# PROB_S7CAS_DDR.net
KiCad netlist of a schematic drawn in Altium Designer
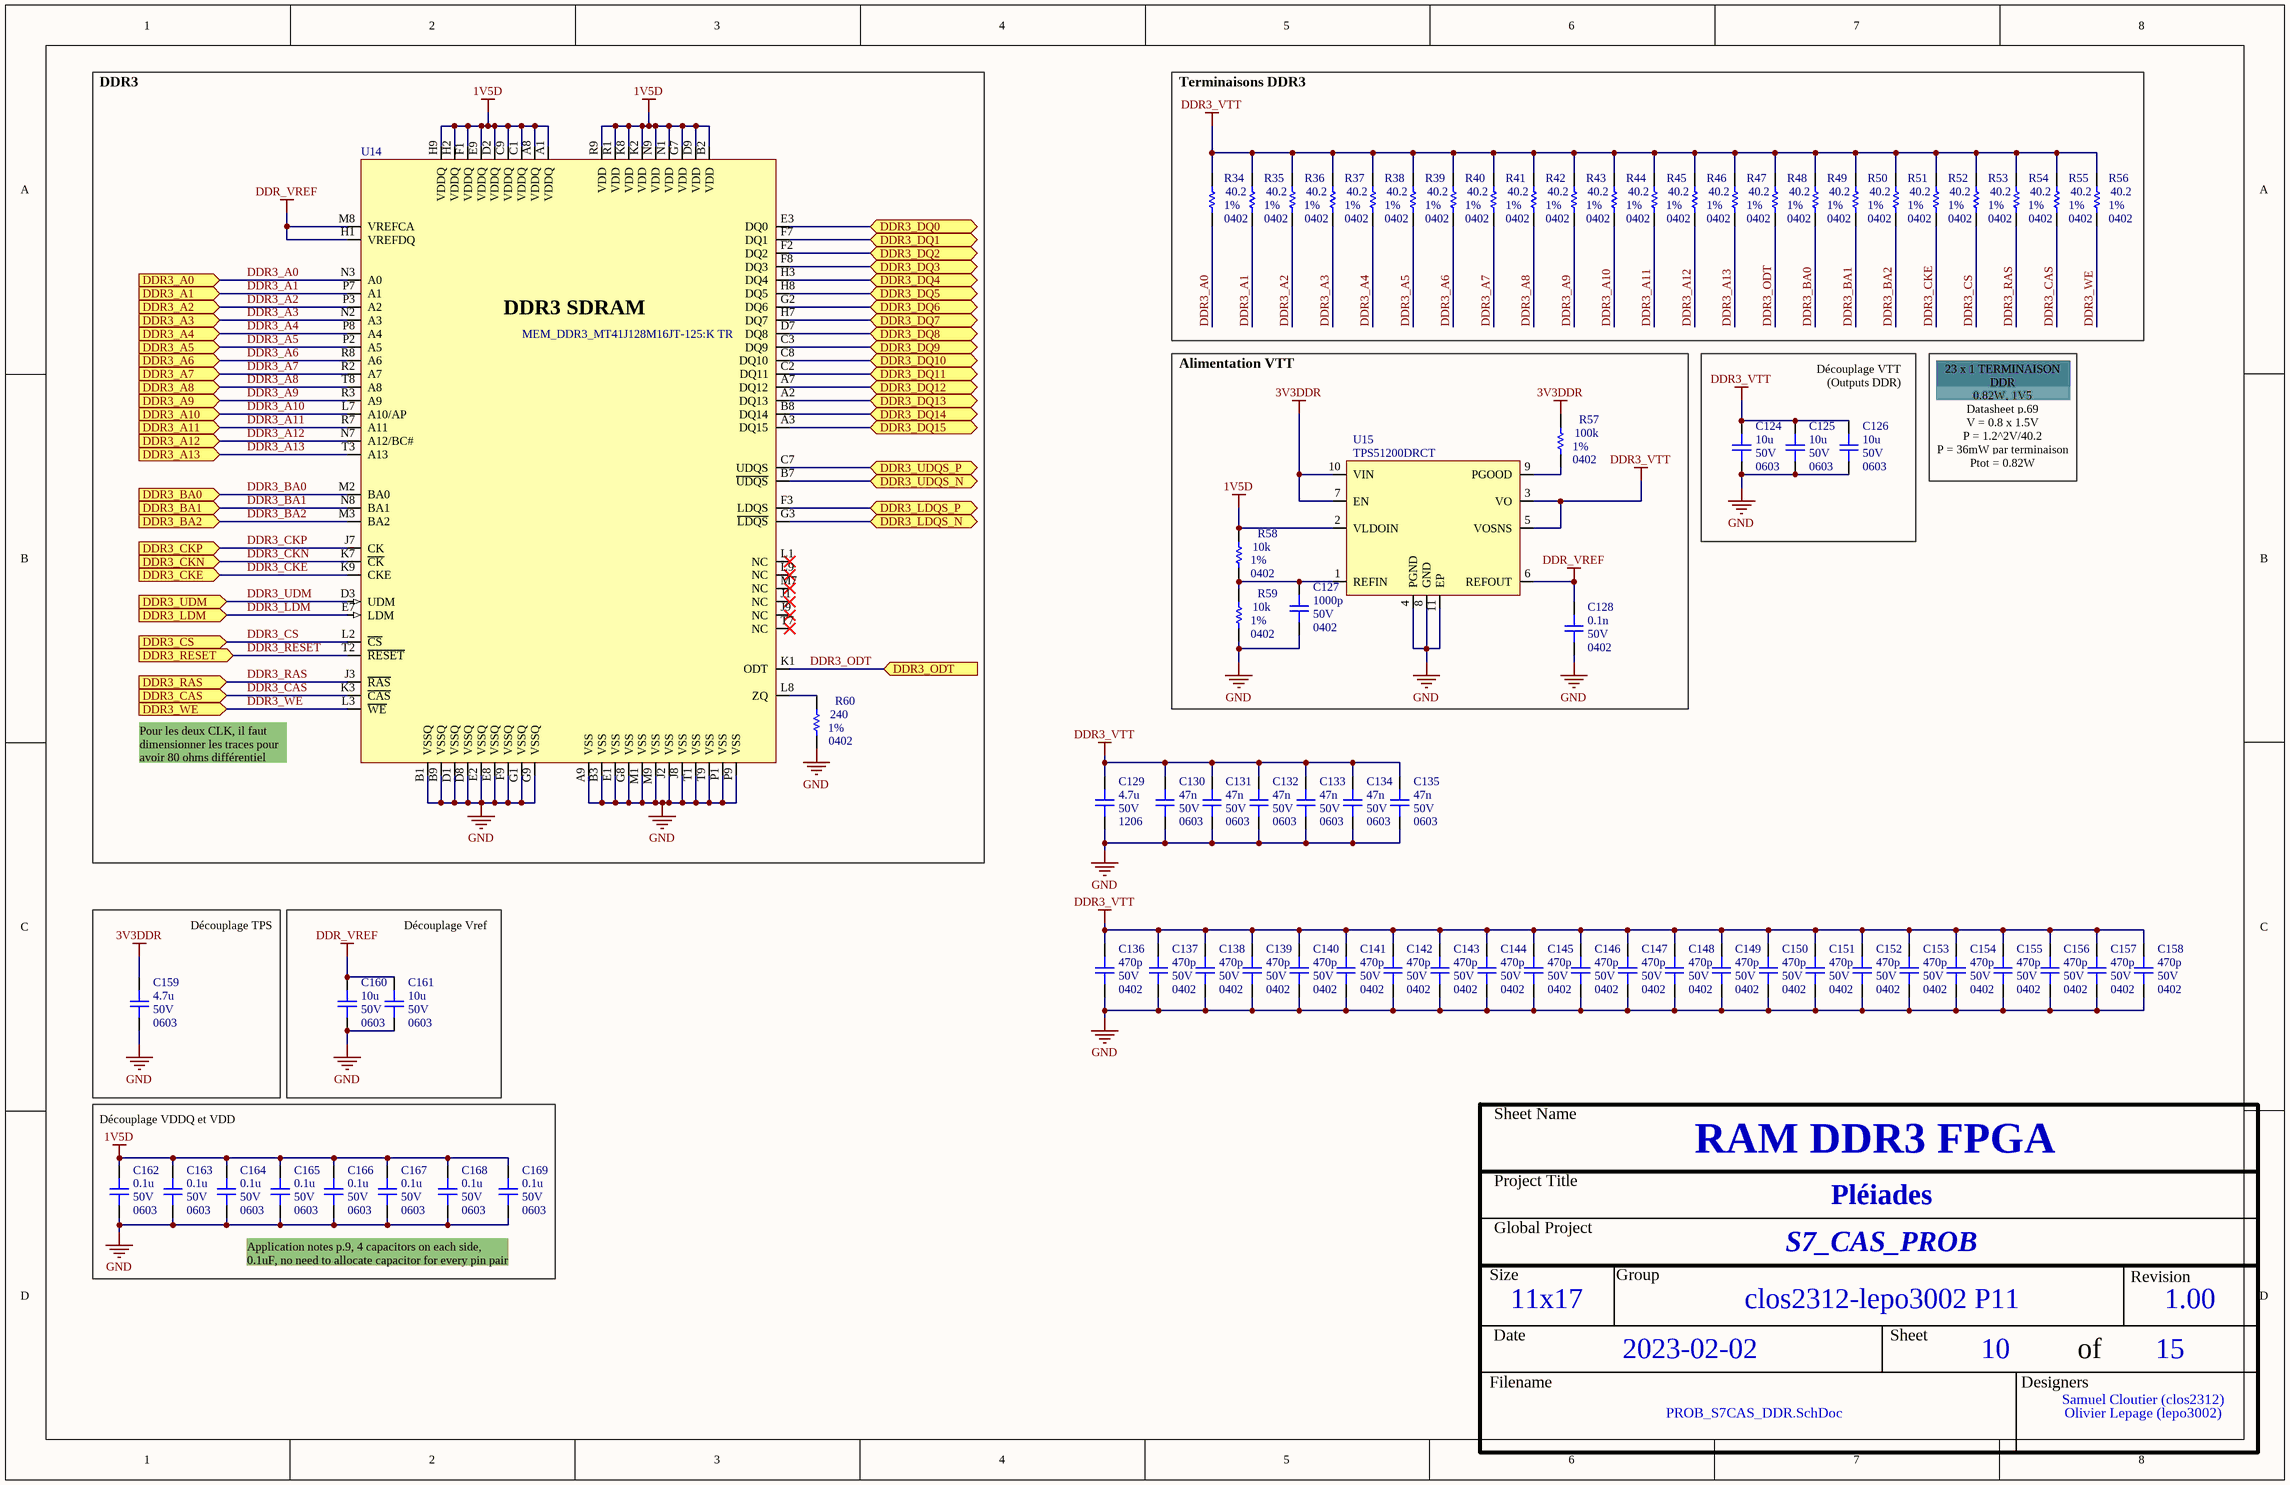
[diagram p0: PROB_S7CAS_DDR.SchDoc]

(export (version "E")
  (design (tool "Eeschema 10.0.6"))
  (components
    (comp (ref "C124")
      (value "10u")
      (footprint "CAP_0603")
      (description "CAP - 0603")
      (fields
        (field (name "VOLTAGE") "50V")
        (field (name "PACKAGE") "0603")
        (field (name "CREATEDBY") "Jonathan Bouchard")
      )
      (libsource (lib "S7CAS_LIB2021") (part "CAP - 0603"))
    )
    (comp (ref "C125")
      (value "10u")
      (footprint "CAP_0603")
      (description "CAP - 0603")
      (fields
        (field (name "VOLTAGE") "50V")
        (field (name "PACKAGE") "0603")
        (field (name "CREATEDBY") "Jonathan Bouchard")
      )
      (libsource (lib "S7CAS_LIB2021") (part "CAP - 0603"))
    )
    (comp (ref "C126")
      (value "10u")
      (footprint "CAP_0603")
      (description "CAP - 0603")
      (fields
        (field (name "VOLTAGE") "50V")
        (field (name "PACKAGE") "0603")
        (field (name "CREATEDBY") "Jonathan Bouchard")
      )
      (libsource (lib "S7CAS_LIB2021") (part "CAP - 0603"))
    )
    (comp (ref "C127")
      (value "1000p")
      (footprint "CAP_0402")
      (description "CAP - 0402")
      (fields
        (field (name "VOLTAGE") "50V")
        (field (name "PACKAGE") "0402")
        (field (name "CREATEDBY") "Jonathan Bouchard")
      )
      (libsource (lib "S7CAS_LIB2021") (part "CAP - 0402"))
    )
    (comp (ref "C128")
      (value "0.1n")
      (footprint "CAP_0402")
      (description "CAP - 0402")
      (fields
        (field (name "VOLTAGE") "50V")
        (field (name "PACKAGE") "0402")
        (field (name "CREATEDBY") "Jonathan Bouchard")
      )
      (libsource (lib "S7CAS_LIB2021") (part "CAP - 0402"))
    )
    (comp (ref "C129")
      (value "4.7u")
      (footprint "CAP_1206")
      (description "CAP - 1206")
      (fields
        (field (name "VOLTAGE") "50V")
        (field (name "PACKAGE") "1206")
        (field (name "CREATEDBY") "Jonathan Bouchard")
      )
      (libsource (lib "S7CAS_LIB2021") (part "CAP - 1206"))
    )
    (comp (ref "C130")
      (value "47n")
      (footprint "CAP_0603")
      (description "CAP - 0603")
      (fields
        (field (name "VOLTAGE") "50V")
        (field (name "PACKAGE") "0603")
        (field (name "CREATEDBY") "Jonathan Bouchard")
      )
      (libsource (lib "S7CAS_LIB2021") (part "CAP - 0603"))
    )
    (comp (ref "C131")
      (value "47n")
      (footprint "CAP_0603")
      (description "CAP - 0603")
      (fields
        (field (name "VOLTAGE") "50V")
        (field (name "PACKAGE") "0603")
        (field (name "CREATEDBY") "Jonathan Bouchard")
      )
      (libsource (lib "S7CAS_LIB2021") (part "CAP - 0603"))
    )
    (comp (ref "C132")
      (value "47n")
      (footprint "CAP_0603")
      (description "CAP - 0603")
      (fields
        (field (name "VOLTAGE") "50V")
        (field (name "PACKAGE") "0603")
        (field (name "CREATEDBY") "Jonathan Bouchard")
      )
      (libsource (lib "S7CAS_LIB2021") (part "CAP - 0603"))
    )
    (comp (ref "C133")
      (value "47n")
      (footprint "CAP_0603")
      (description "CAP - 0603")
      (fields
        (field (name "VOLTAGE") "50V")
        (field (name "PACKAGE") "0603")
        (field (name "CREATEDBY") "Jonathan Bouchard")
      )
      (libsource (lib "S7CAS_LIB2021") (part "CAP - 0603"))
    )
    (comp (ref "C134")
      (value "47n")
      (footprint "CAP_0603")
      (description "CAP - 0603")
      (fields
        (field (name "VOLTAGE") "50V")
        (field (name "PACKAGE") "0603")
        (field (name "CREATEDBY") "Jonathan Bouchard")
      )
      (libsource (lib "S7CAS_LIB2021") (part "CAP - 0603"))
    )
    (comp (ref "C135")
      (value "47n")
      (footprint "CAP_0603")
      (description "CAP - 0603")
      (fields
        (field (name "VOLTAGE") "50V")
        (field (name "PACKAGE") "0603")
        (field (name "CREATEDBY") "Jonathan Bouchard")
      )
      (libsource (lib "S7CAS_LIB2021") (part "CAP - 0603"))
    )
    (comp (ref "C136")
      (value "470p")
      (footprint "CAP_0402")
      (description "CAP - 0402")
      (fields
        (field (name "VOLTAGE") "50V")
        (field (name "PACKAGE") "0402")
        (field (name "CREATEDBY") "Jonathan Bouchard")
      )
      (libsource (lib "S7CAS_LIB2021") (part "CAP - 0402"))
    )
    (comp (ref "C137")
      (value "470p")
      (footprint "CAP_0402")
      (description "CAP - 0402")
      (fields
        (field (name "VOLTAGE") "50V")
        (field (name "PACKAGE") "0402")
        (field (name "CREATEDBY") "Jonathan Bouchard")
      )
      (libsource (lib "S7CAS_LIB2021") (part "CAP - 0402"))
    )
    (comp (ref "C138")
      (value "470p")
      (footprint "CAP_0402")
      (description "CAP - 0402")
      (fields
        (field (name "VOLTAGE") "50V")
        (field (name "PACKAGE") "0402")
        (field (name "CREATEDBY") "Jonathan Bouchard")
      )
      (libsource (lib "S7CAS_LIB2021") (part "CAP - 0402"))
    )
    (comp (ref "C139")
      (value "470p")
      (footprint "CAP_0402")
      (description "CAP - 0402")
      (fields
        (field (name "VOLTAGE") "50V")
        (field (name "PACKAGE") "0402")
        (field (name "CREATEDBY") "Jonathan Bouchard")
      )
      (libsource (lib "S7CAS_LIB2021") (part "CAP - 0402"))
    )
    (comp (ref "C140")
      (value "470p")
      (footprint "CAP_0402")
      (description "CAP - 0402")
      (fields
        (field (name "VOLTAGE") "50V")
        (field (name "PACKAGE") "0402")
        (field (name "CREATEDBY") "Jonathan Bouchard")
      )
      (libsource (lib "S7CAS_LIB2021") (part "CAP - 0402"))
    )
    (comp (ref "C141")
      (value "470p")
      (footprint "CAP_0402")
      (description "CAP - 0402")
      (fields
        (field (name "VOLTAGE") "50V")
        (field (name "PACKAGE") "0402")
        (field (name "CREATEDBY") "Jonathan Bouchard")
      )
      (libsource (lib "S7CAS_LIB2021") (part "CAP - 0402"))
    )
    (comp (ref "C142")
      (value "470p")
      (footprint "CAP_0402")
      (description "CAP - 0402")
      (fields
        (field (name "VOLTAGE") "50V")
        (field (name "PACKAGE") "0402")
        (field (name "CREATEDBY") "Jonathan Bouchard")
      )
      (libsource (lib "S7CAS_LIB2021") (part "CAP - 0402"))
    )
    (comp (ref "C143")
      (value "470p")
      (footprint "CAP_0402")
      (description "CAP - 0402")
      (fields
        (field (name "VOLTAGE") "50V")
        (field (name "PACKAGE") "0402")
        (field (name "CREATEDBY") "Jonathan Bouchard")
      )
      (libsource (lib "S7CAS_LIB2021") (part "CAP - 0402"))
    )
    (comp (ref "C144")
      (value "470p")
      (footprint "CAP_0402")
      (description "CAP - 0402")
      (fields
        (field (name "VOLTAGE") "50V")
        (field (name "PACKAGE") "0402")
        (field (name "CREATEDBY") "Jonathan Bouchard")
      )
      (libsource (lib "S7CAS_LIB2021") (part "CAP - 0402"))
    )
    (comp (ref "C145")
      (value "470p")
      (footprint "CAP_0402")
      (description "CAP - 0402")
      (fields
        (field (name "VOLTAGE") "50V")
        (field (name "PACKAGE") "0402")
        (field (name "CREATEDBY") "Jonathan Bouchard")
      )
      (libsource (lib "S7CAS_LIB2021") (part "CAP - 0402"))
    )
    (comp (ref "C146")
      (value "470p")
      (footprint "CAP_0402")
      (description "CAP - 0402")
      (fields
        (field (name "VOLTAGE") "50V")
        (field (name "PACKAGE") "0402")
        (field (name "CREATEDBY") "Jonathan Bouchard")
      )
      (libsource (lib "S7CAS_LIB2021") (part "CAP - 0402"))
    )
    (comp (ref "C147")
      (value "470p")
      (footprint "CAP_0402")
      (description "CAP - 0402")
      (fields
        (field (name "VOLTAGE") "50V")
        (field (name "PACKAGE") "0402")
        (field (name "CREATEDBY") "Jonathan Bouchard")
      )
      (libsource (lib "S7CAS_LIB2021") (part "CAP - 0402"))
    )
    (comp (ref "C148")
      (value "470p")
      (footprint "CAP_0402")
      (description "CAP - 0402")
      (fields
        (field (name "VOLTAGE") "50V")
        (field (name "PACKAGE") "0402")
        (field (name "CREATEDBY") "Jonathan Bouchard")
      )
      (libsource (lib "S7CAS_LIB2021") (part "CAP - 0402"))
    )
    (comp (ref "C149")
      (value "470p")
      (footprint "CAP_0402")
      (description "CAP - 0402")
      (fields
        (field (name "VOLTAGE") "50V")
        (field (name "PACKAGE") "0402")
        (field (name "CREATEDBY") "Jonathan Bouchard")
      )
      (libsource (lib "S7CAS_LIB2021") (part "CAP - 0402"))
    )
    (comp (ref "C150")
      (value "470p")
      (footprint "CAP_0402")
      (description "CAP - 0402")
      (fields
        (field (name "VOLTAGE") "50V")
        (field (name "PACKAGE") "0402")
        (field (name "CREATEDBY") "Jonathan Bouchard")
      )
      (libsource (lib "S7CAS_LIB2021") (part "CAP - 0402"))
    )
    (comp (ref "C151")
      (value "470p")
      (footprint "CAP_0402")
      (description "CAP - 0402")
      (fields
        (field (name "VOLTAGE") "50V")
        (field (name "PACKAGE") "0402")
        (field (name "CREATEDBY") "Jonathan Bouchard")
      )
      (libsource (lib "S7CAS_LIB2021") (part "CAP - 0402"))
    )
    (comp (ref "C152")
      (value "470p")
      (footprint "CAP_0402")
      (description "CAP - 0402")
      (fields
        (field (name "VOLTAGE") "50V")
        (field (name "PACKAGE") "0402")
        (field (name "CREATEDBY") "Jonathan Bouchard")
      )
      (libsource (lib "S7CAS_LIB2021") (part "CAP - 0402"))
    )
    (comp (ref "C153")
      (value "470p")
      (footprint "CAP_0402")
      (description "CAP - 0402")
      (fields
        (field (name "VOLTAGE") "50V")
        (field (name "PACKAGE") "0402")
        (field (name "CREATEDBY") "Jonathan Bouchard")
      )
      (libsource (lib "S7CAS_LIB2021") (part "CAP - 0402"))
    )
    (comp (ref "C154")
      (value "470p")
      (footprint "CAP_0402")
      (description "CAP - 0402")
      (fields
        (field (name "VOLTAGE") "50V")
        (field (name "PACKAGE") "0402")
        (field (name "CREATEDBY") "Jonathan Bouchard")
      )
      (libsource (lib "S7CAS_LIB2021") (part "CAP - 0402"))
    )
    (comp (ref "C155")
      (value "470p")
      (footprint "CAP_0402")
      (description "CAP - 0402")
      (fields
        (field (name "VOLTAGE") "50V")
        (field (name "PACKAGE") "0402")
        (field (name "CREATEDBY") "Jonathan Bouchard")
      )
      (libsource (lib "S7CAS_LIB2021") (part "CAP - 0402"))
    )
    (comp (ref "C156")
      (value "470p")
      (footprint "CAP_0402")
      (description "CAP - 0402")
      (fields
        (field (name "VOLTAGE") "50V")
        (field (name "PACKAGE") "0402")
        (field (name "CREATEDBY") "Jonathan Bouchard")
      )
      (libsource (lib "S7CAS_LIB2021") (part "CAP - 0402"))
    )
    (comp (ref "C157")
      (value "470p")
      (footprint "CAP_0402")
      (description "CAP - 0402")
      (fields
        (field (name "VOLTAGE") "50V")
        (field (name "PACKAGE") "0402")
        (field (name "CREATEDBY") "Jonathan Bouchard")
      )
      (libsource (lib "S7CAS_LIB2021") (part "CAP - 0402"))
    )
    (comp (ref "C158")
      (value "470p")
      (footprint "CAP_0402")
      (description "CAP - 0402")
      (fields
        (field (name "VOLTAGE") "50V")
        (field (name "PACKAGE") "0402")
        (field (name "CREATEDBY") "Jonathan Bouchard")
      )
      (libsource (lib "S7CAS_LIB2021") (part "CAP - 0402"))
    )
    (comp (ref "C159")
      (value "4.7u")
      (footprint "CAP_0603")
      (description "CAP - 0603")
      (fields
        (field (name "VOLTAGE") "50V")
        (field (name "PACKAGE") "0603")
        (field (name "CREATEDBY") "Jonathan Bouchard")
      )
      (libsource (lib "S7CAS_LIB2021") (part "CAP - 0603"))
    )
    (comp (ref "C160")
      (value "10u")
      (footprint "CAP_0603")
      (description "CAP - 0603")
      (fields
        (field (name "VOLTAGE") "50V")
        (field (name "PACKAGE") "0603")
        (field (name "CREATEDBY") "Jonathan Bouchard")
      )
      (libsource (lib "S7CAS_LIB2021") (part "CAP - 0603"))
    )
    (comp (ref "C161")
      (value "10u")
      (footprint "CAP_0603")
      (description "CAP - 0603")
      (fields
        (field (name "VOLTAGE") "50V")
        (field (name "PACKAGE") "0603")
        (field (name "CREATEDBY") "Jonathan Bouchard")
      )
      (libsource (lib "S7CAS_LIB2021") (part "CAP - 0603"))
    )
    (comp (ref "C162")
      (value "0.1u")
      (footprint "CAP_0603")
      (description "CAP - 0603")
      (fields
        (field (name "VOLTAGE") "50V")
        (field (name "PACKAGE") "0603")
        (field (name "CREATEDBY") "Jonathan Bouchard")
      )
      (libsource (lib "S7CAS_LIB2021") (part "CAP - 0603"))
    )
    (comp (ref "C163")
      (value "0.1u")
      (footprint "CAP_0603")
      (description "CAP - 0603")
      (fields
        (field (name "VOLTAGE") "50V")
        (field (name "PACKAGE") "0603")
        (field (name "CREATEDBY") "Jonathan Bouchard")
      )
      (libsource (lib "S7CAS_LIB2021") (part "CAP - 0603"))
    )
    (comp (ref "C164")
      (value "0.1u")
      (footprint "CAP_0603")
      (description "CAP - 0603")
      (fields
        (field (name "VOLTAGE") "50V")
        (field (name "PACKAGE") "0603")
        (field (name "CREATEDBY") "Jonathan Bouchard")
      )
      (libsource (lib "S7CAS_LIB2021") (part "CAP - 0603"))
    )
    (comp (ref "C165")
      (value "0.1u")
      (footprint "CAP_0603")
      (description "CAP - 0603")
      (fields
        (field (name "VOLTAGE") "50V")
        (field (name "PACKAGE") "0603")
        (field (name "CREATEDBY") "Jonathan Bouchard")
      )
      (libsource (lib "S7CAS_LIB2021") (part "CAP - 0603"))
    )
    (comp (ref "C166")
      (value "0.1u")
      (footprint "CAP_0603")
      (description "CAP - 0603")
      (fields
        (field (name "VOLTAGE") "50V")
        (field (name "PACKAGE") "0603")
        (field (name "CREATEDBY") "Jonathan Bouchard")
      )
      (libsource (lib "S7CAS_LIB2021") (part "CAP - 0603"))
    )
    (comp (ref "C167")
      (value "0.1u")
      (footprint "CAP_0603")
      (description "CAP - 0603")
      (fields
        (field (name "VOLTAGE") "50V")
        (field (name "PACKAGE") "0603")
        (field (name "CREATEDBY") "Jonathan Bouchard")
      )
      (libsource (lib "S7CAS_LIB2021") (part "CAP - 0603"))
    )
    (comp (ref "C168")
      (value "0.1u")
      (footprint "CAP_0603")
      (description "CAP - 0603")
      (fields
        (field (name "VOLTAGE") "50V")
        (field (name "PACKAGE") "0603")
        (field (name "CREATEDBY") "Jonathan Bouchard")
      )
      (libsource (lib "S7CAS_LIB2021") (part "CAP - 0603"))
    )
    (comp (ref "C169")
      (value "0.1u")
      (footprint "CAP_0603")
      (description "CAP - 0603")
      (fields
        (field (name "VOLTAGE") "50V")
        (field (name "PACKAGE") "0603")
        (field (name "CREATEDBY") "Jonathan Bouchard")
      )
      (libsource (lib "S7CAS_LIB2021") (part "CAP - 0603"))
    )
    (comp (ref "R34")
      (value "40.2")
      (footprint "RES_0402")
      (description "RES - 0402")
      (fields
        (field (name "VOLTAGE") "50V")
        (field (name "POWER") "1/16W")
        (field (name "PACKAGE") "0402")
        (field (name "PRECISION") "1%")
        (field (name "CREATEDBY") "Jonathan Bouchard")
      )
      (libsource (lib "S7CAS_LIB2021") (part "RES - 0402"))
    )
    (comp (ref "R35")
      (value "40.2")
      (footprint "RES_0402")
      (description "RES - 0402")
      (fields
        (field (name "VOLTAGE") "50V")
        (field (name "POWER") "1/16W")
        (field (name "PACKAGE") "0402")
        (field (name "PRECISION") "1%")
        (field (name "CREATEDBY") "Jonathan Bouchard")
      )
      (libsource (lib "S7CAS_LIB2021") (part "RES - 0402"))
    )
    (comp (ref "R36")
      (value "40.2")
      (footprint "RES_0402")
      (description "RES - 0402")
      (fields
        (field (name "VOLTAGE") "50V")
        (field (name "POWER") "1/16W")
        (field (name "PACKAGE") "0402")
        (field (name "PRECISION") "1%")
        (field (name "CREATEDBY") "Jonathan Bouchard")
      )
      (libsource (lib "S7CAS_LIB2021") (part "RES - 0402"))
    )
    (comp (ref "R37")
      (value "40.2")
      (footprint "RES_0402")
      (description "RES - 0402")
      (fields
        (field (name "VOLTAGE") "50V")
        (field (name "POWER") "1/16W")
        (field (name "PACKAGE") "0402")
        (field (name "PRECISION") "1%")
        (field (name "CREATEDBY") "Jonathan Bouchard")
      )
      (libsource (lib "S7CAS_LIB2021") (part "RES - 0402"))
    )
    (comp (ref "R38")
      (value "40.2")
      (footprint "RES_0402")
      (description "RES - 0402")
      (fields
        (field (name "VOLTAGE") "50V")
        (field (name "POWER") "1/16W")
        (field (name "PACKAGE") "0402")
        (field (name "PRECISION") "1%")
        (field (name "CREATEDBY") "Jonathan Bouchard")
      )
      (libsource (lib "S7CAS_LIB2021") (part "RES - 0402"))
    )
    (comp (ref "R39")
      (value "40.2")
      (footprint "RES_0402")
      (description "RES - 0402")
      (fields
        (field (name "VOLTAGE") "50V")
        (field (name "POWER") "1/16W")
        (field (name "PACKAGE") "0402")
        (field (name "PRECISION") "1%")
        (field (name "CREATEDBY") "Jonathan Bouchard")
      )
      (libsource (lib "S7CAS_LIB2021") (part "RES - 0402"))
    )
    (comp (ref "R40")
      (value "40.2")
      (footprint "RES_0402")
      (description "RES - 0402")
      (fields
        (field (name "VOLTAGE") "50V")
        (field (name "POWER") "1/16W")
        (field (name "PACKAGE") "0402")
        (field (name "PRECISION") "1%")
        (field (name "CREATEDBY") "Jonathan Bouchard")
      )
      (libsource (lib "S7CAS_LIB2021") (part "RES - 0402"))
    )
    (comp (ref "R41")
      (value "40.2")
      (footprint "RES_0402")
      (description "RES - 0402")
      (fields
        (field (name "VOLTAGE") "50V")
        (field (name "POWER") "1/16W")
        (field (name "PACKAGE") "0402")
        (field (name "PRECISION") "1%")
        (field (name "CREATEDBY") "Jonathan Bouchard")
      )
      (libsource (lib "S7CAS_LIB2021") (part "RES - 0402"))
    )
    (comp (ref "R42")
      (value "40.2")
      (footprint "RES_0402")
      (description "RES - 0402")
      (fields
        (field (name "VOLTAGE") "50V")
        (field (name "POWER") "1/16W")
        (field (name "PACKAGE") "0402")
        (field (name "PRECISION") "1%")
        (field (name "CREATEDBY") "Jonathan Bouchard")
      )
      (libsource (lib "S7CAS_LIB2021") (part "RES - 0402"))
    )
    (comp (ref "R43")
      (value "40.2")
      (footprint "RES_0402")
      (description "RES - 0402")
      (fields
        (field (name "VOLTAGE") "50V")
        (field (name "POWER") "1/16W")
        (field (name "PACKAGE") "0402")
        (field (name "PRECISION") "1%")
        (field (name "CREATEDBY") "Jonathan Bouchard")
      )
      (libsource (lib "S7CAS_LIB2021") (part "RES - 0402"))
    )
    (comp (ref "R44")
      (value "40.2")
      (footprint "RES_0402")
      (description "RES - 0402")
      (fields
        (field (name "VOLTAGE") "50V")
        (field (name "POWER") "1/16W")
        (field (name "PACKAGE") "0402")
        (field (name "PRECISION") "1%")
        (field (name "CREATEDBY") "Jonathan Bouchard")
      )
      (libsource (lib "S7CAS_LIB2021") (part "RES - 0402"))
    )
    (comp (ref "R45")
      (value "40.2")
      (footprint "RES_0402")
      (description "RES - 0402")
      (fields
        (field (name "VOLTAGE") "50V")
        (field (name "POWER") "1/16W")
        (field (name "PACKAGE") "0402")
        (field (name "PRECISION") "1%")
        (field (name "CREATEDBY") "Jonathan Bouchard")
      )
      (libsource (lib "S7CAS_LIB2021") (part "RES - 0402"))
    )
    (comp (ref "R46")
      (value "40.2")
      (footprint "RES_0402")
      (description "RES - 0402")
      (fields
        (field (name "VOLTAGE") "50V")
        (field (name "POWER") "1/16W")
        (field (name "PACKAGE") "0402")
        (field (name "PRECISION") "1%")
        (field (name "CREATEDBY") "Jonathan Bouchard")
      )
      (libsource (lib "S7CAS_LIB2021") (part "RES - 0402"))
    )
    (comp (ref "R47")
      (value "40.2")
      (footprint "RES_0402")
      (description "RES - 0402")
      (fields
        (field (name "VOLTAGE") "50V")
        (field (name "POWER") "1/16W")
        (field (name "PACKAGE") "0402")
        (field (name "PRECISION") "1%")
        (field (name "CREATEDBY") "Jonathan Bouchard")
      )
      (libsource (lib "S7CAS_LIB2021") (part "RES - 0402"))
    )
    (comp (ref "R48")
      (value "40.2")
      (footprint "RES_0402")
      (description "RES - 0402")
      (fields
        (field (name "VOLTAGE") "50V")
        (field (name "POWER") "1/16W")
        (field (name "PACKAGE") "0402")
        (field (name "PRECISION") "1%")
        (field (name "CREATEDBY") "Jonathan Bouchard")
      )
      (libsource (lib "S7CAS_LIB2021") (part "RES - 0402"))
    )
    (comp (ref "R49")
      (value "40.2")
      (footprint "RES_0402")
      (description "RES - 0402")
      (fields
        (field (name "VOLTAGE") "50V")
        (field (name "POWER") "1/16W")
        (field (name "PACKAGE") "0402")
        (field (name "PRECISION") "1%")
        (field (name "CREATEDBY") "Jonathan Bouchard")
      )
      (libsource (lib "S7CAS_LIB2021") (part "RES - 0402"))
    )
    (comp (ref "R50")
      (value "40.2")
      (footprint "RES_0402")
      (description "RES - 0402")
      (fields
        (field (name "VOLTAGE") "50V")
        (field (name "POWER") "1/16W")
        (field (name "PACKAGE") "0402")
        (field (name "PRECISION") "1%")
        (field (name "CREATEDBY") "Jonathan Bouchard")
      )
      (libsource (lib "S7CAS_LIB2021") (part "RES - 0402"))
    )
    (comp (ref "R51")
      (value "40.2")
      (footprint "RES_0402")
      (description "RES - 0402")
      (fields
        (field (name "VOLTAGE") "50V")
        (field (name "POWER") "1/16W")
        (field (name "PACKAGE") "0402")
        (field (name "PRECISION") "1%")
        (field (name "CREATEDBY") "Jonathan Bouchard")
      )
      (libsource (lib "S7CAS_LIB2021") (part "RES - 0402"))
    )
    (comp (ref "R52")
      (value "40.2")
      (footprint "RES_0402")
      (description "RES - 0402")
      (fields
        (field (name "VOLTAGE") "50V")
        (field (name "POWER") "1/16W")
        (field (name "PACKAGE") "0402")
        (field (name "PRECISION") "1%")
        (field (name "CREATEDBY") "Jonathan Bouchard")
      )
      (libsource (lib "S7CAS_LIB2021") (part "RES - 0402"))
    )
    (comp (ref "R53")
      (value "40.2")
      (footprint "RES_0402")
      (description "RES - 0402")
      (fields
        (field (name "VOLTAGE") "50V")
        (field (name "POWER") "1/16W")
        (field (name "PACKAGE") "0402")
        (field (name "PRECISION") "1%")
        (field (name "CREATEDBY") "Jonathan Bouchard")
      )
      (libsource (lib "S7CAS_LIB2021") (part "RES - 0402"))
    )
    (comp (ref "R54")
      (value "40.2")
      (footprint "RES_0402")
      (description "RES - 0402")
      (fields
        (field (name "VOLTAGE") "50V")
        (field (name "POWER") "1/16W")
        (field (name "PACKAGE") "0402")
        (field (name "PRECISION") "1%")
        (field (name "CREATEDBY") "Jonathan Bouchard")
      )
      (libsource (lib "S7CAS_LIB2021") (part "RES - 0402"))
    )
    (comp (ref "R55")
      (value "40.2")
      (footprint "RES_0402")
      (description "RES - 0402")
      (fields
        (field (name "VOLTAGE") "50V")
        (field (name "POWER") "1/16W")
        (field (name "PACKAGE") "0402")
        (field (name "PRECISION") "1%")
        (field (name "CREATEDBY") "Jonathan Bouchard")
      )
      (libsource (lib "S7CAS_LIB2021") (part "RES - 0402"))
    )
    (comp (ref "R56")
      (value "40.2")
      (footprint "RES_0402")
      (description "RES - 0402")
      (fields
        (field (name "VOLTAGE") "50V")
        (field (name "POWER") "1/16W")
        (field (name "PACKAGE") "0402")
        (field (name "PRECISION") "1%")
        (field (name "CREATEDBY") "Jonathan Bouchard")
      )
      (libsource (lib "S7CAS_LIB2021") (part "RES - 0402"))
    )
    (comp (ref "R57")
      (value "100k")
      (footprint "RES_0402")
      (description "RES - 0402")
      (fields
        (field (name "VOLTAGE") "50V")
        (field (name "POWER") "1/16W")
        (field (name "PACKAGE") "0402")
        (field (name "PRECISION") "1%")
        (field (name "CREATEDBY") "Jonathan Bouchard")
      )
      (libsource (lib "S7CAS_LIB2021") (part "RES - 0402"))
    )
    (comp (ref "R58")
      (value "10k")
      (footprint "RES_0402")
      (description "RES - 0402")
      (fields
        (field (name "VOLTAGE") "50V")
        (field (name "POWER") "1/16W")
        (field (name "PACKAGE") "0402")
        (field (name "PRECISION") "1%")
        (field (name "CREATEDBY") "Jonathan Bouchard")
      )
      (libsource (lib "S7CAS_LIB2021") (part "RES - 0402"))
    )
    (comp (ref "R59")
      (value "10k")
      (footprint "RES_0402")
      (description "RES - 0402")
      (fields
        (field (name "VOLTAGE") "50V")
        (field (name "POWER") "1/16W")
        (field (name "PACKAGE") "0402")
        (field (name "PRECISION") "1%")
        (field (name "CREATEDBY") "Jonathan Bouchard")
      )
      (libsource (lib "S7CAS_LIB2021") (part "RES - 0402"))
    )
    (comp (ref "R60")
      (value "240")
      (footprint "RES_0402")
      (description "RES - 0402")
      (fields
        (field (name "VOLTAGE") "50V")
        (field (name "POWER") "1/16W")
        (field (name "PACKAGE") "0402")
        (field (name "PRECISION") "1%")
        (field (name "CREATEDBY") "Jonathan Bouchard")
      )
      (libsource (lib "S7CAS_LIB2021") (part "RES - 0402"))
    )
    (comp (ref "U14")
      (value "MEM_DDR3_MT41J128M16JT-125:K TR")
      (footprint "MEM_DDR3_MT41J128M16JT-125")
      (description "MEM - DDR3 SDRAM 2GBIT 800MHZ - TFBGA-96")
      (fields
        (field (name "VOLTAGE") "1.425 V ~ 1.575 V")
        (field (name "MFG") "Micrel")
        (field (name "CREATEDBY") "Jonathan Bouchard")
      )
      (libsource (lib "S7CAS_LIB2021") (part "MEM_DDR3_MT41J128M16JT-125{colon}K TR"))
    )
    (comp (ref "U15")
      (value "TPS51200DRCT")
      (footprint "REG_PMIC_TPS51200DRCT")
      (description "REG - DDR TERMINATION/REF REG - 10-VFDFN")
      (fields
        (field (name "CREATEDBY/DATE") "Joel Lemay 2019-03-19")
        (field (name "VERIFIEDBY") "Nicolas V. (2019-05-31)")
      )
      (libsource (lib "S7CAS_LIB2021") (part "REG_PMIC_TPS51200DRCT"))
    )
  )
  (nets
    (net (code "1") (name "/DDR3_A0") (class "Default")
      (node (ref "R34") (pin "1") (pinfunction "1_1") (pintype "passive"))
      (node (ref "U14") (pin "N3") (pinfunction "A0_N3") (pintype "passive"))
    )
    (net (code "2") (name "/DDR3_A1") (class "Default")
      (node (ref "R35") (pin "1") (pinfunction "1_1") (pintype "passive"))
      (node (ref "U14") (pin "P7") (pinfunction "A1_P7") (pintype "passive"))
    )
    (net (code "3") (name "/DDR3_A2") (class "Default")
      (node (ref "R36") (pin "1") (pinfunction "1_1") (pintype "passive"))
      (node (ref "U14") (pin "P3") (pinfunction "A2_P3") (pintype "passive"))
    )
    (net (code "4") (name "/DDR3_A3") (class "Default")
      (node (ref "R37") (pin "1") (pinfunction "1_1") (pintype "passive"))
      (node (ref "U14") (pin "N2") (pinfunction "A3_N2") (pintype "passive"))
    )
    (net (code "5") (name "/DDR3_A4") (class "Default")
      (node (ref "R38") (pin "1") (pinfunction "1_1") (pintype "passive"))
      (node (ref "U14") (pin "P8") (pinfunction "A4_P8") (pintype "passive"))
    )
    (net (code "6") (name "/DDR3_A5") (class "Default")
      (node (ref "R39") (pin "1") (pinfunction "1_1") (pintype "passive"))
      (node (ref "U14") (pin "P2") (pinfunction "A5_P2") (pintype "passive"))
    )
    (net (code "7") (name "/DDR3_A6") (class "Default")
      (node (ref "R40") (pin "1") (pinfunction "1_1") (pintype "passive"))
      (node (ref "U14") (pin "R8") (pinfunction "A6_R8") (pintype "passive"))
    )
    (net (code "8") (name "/DDR3_A7") (class "Default")
      (node (ref "R41") (pin "1") (pinfunction "1_1") (pintype "passive"))
      (node (ref "U14") (pin "R2") (pinfunction "A7_R2") (pintype "passive"))
    )
    (net (code "9") (name "/DDR3_A8") (class "Default")
      (node (ref "R42") (pin "1") (pinfunction "1_1") (pintype "passive"))
      (node (ref "U14") (pin "T8") (pinfunction "A8_T8") (pintype "passive"))
    )
    (net (code "10") (name "/DDR3_A9") (class "Default")
      (node (ref "R43") (pin "1") (pinfunction "1_1") (pintype "passive"))
      (node (ref "U14") (pin "R3") (pinfunction "A9_R3") (pintype "passive"))
    )
    (net (code "11") (name "/DDR3_A10") (class "Default")
      (node (ref "R44") (pin "1") (pinfunction "1_1") (pintype "passive"))
      (node (ref "U14") (pin "L7") (pinfunction "A10/AP_L7") (pintype "passive"))
    )
    (net (code "12") (name "/DDR3_A11") (class "Default")
      (node (ref "R45") (pin "1") (pinfunction "1_1") (pintype "passive"))
      (node (ref "U14") (pin "R7") (pinfunction "A11_R7") (pintype "passive"))
    )
    (net (code "13") (name "/DDR3_A12") (class "Default")
      (node (ref "R46") (pin "1") (pinfunction "1_1") (pintype "passive"))
      (node (ref "U14") (pin "N7") (pinfunction "A12/BC#_N7") (pintype "passive"))
    )
    (net (code "14") (name "/DDR3_A13") (class "Default")
      (node (ref "R47") (pin "1") (pinfunction "1_1") (pintype "passive"))
      (node (ref "U14") (pin "T3") (pinfunction "A13_T3") (pintype "passive"))
    )
    (net (code "15") (name "/DDR3_BA0") (class "Default")
      (node (ref "R49") (pin "1") (pinfunction "1_1") (pintype "passive"))
      (node (ref "U14") (pin "M2") (pinfunction "BA0_M2") (pintype "passive"))
    )
    (net (code "16") (name "/DDR3_BA1") (class "Default")
      (node (ref "R50") (pin "1") (pinfunction "1_1") (pintype "passive"))
      (node (ref "U14") (pin "N8") (pinfunction "BA1_N8") (pintype "passive"))
    )
    (net (code "17") (name "/DDR3_BA2") (class "Default")
      (node (ref "R51") (pin "1") (pinfunction "1_1") (pintype "passive"))
      (node (ref "U14") (pin "M3") (pinfunction "BA2_M3") (pintype "passive"))
    )
    (net (code "18") (name "/DDR3_CAS") (class "Default")
      (node (ref "R55") (pin "1") (pinfunction "1_1") (pintype "passive"))
      (node (ref "U14") (pin "K3") (pinfunction "CAS_K3") (pintype "passive"))
    )
    (net (code "19") (name "/DDR3_CKE") (class "Default")
      (node (ref "R52") (pin "1") (pinfunction "1_1") (pintype "passive"))
      (node (ref "U14") (pin "K9") (pinfunction "CKE_K9") (pintype "passive"))
    )
    (net (code "20") (name "/DDR3_CKN") (class "Default")
      (node (ref "U14") (pin "K7") (pinfunction "CK_K7") (pintype "passive"))
    )
    (net (code "21") (name "/DDR3_CKP") (class "Default")
      (node (ref "U14") (pin "J7") (pinfunction "CK_J7") (pintype "passive"))
    )
    (net (code "22") (name "/DDR3_CS") (class "Default")
      (node (ref "R53") (pin "1") (pinfunction "1_1") (pintype "passive"))
      (node (ref "U14") (pin "L2") (pinfunction "CS_L2") (pintype "passive"))
    )
    (net (code "23") (name "/DDR3_DQ0") (class "Default")
      (node (ref "U14") (pin "E3") (pinfunction "DQ0_E3") (pintype "passive"))
    )
    (net (code "24") (name "/DDR3_DQ1") (class "Default")
      (node (ref "U14") (pin "F7") (pinfunction "DQ1_F7") (pintype "passive"))
    )
    (net (code "25") (name "/DDR3_DQ2") (class "Default")
      (node (ref "U14") (pin "F2") (pinfunction "DQ2_F2") (pintype "passive"))
    )
    (net (code "26") (name "/DDR3_DQ3") (class "Default")
      (node (ref "U14") (pin "F8") (pinfunction "DQ3_F8") (pintype "passive"))
    )
    (net (code "27") (name "/DDR3_DQ4") (class "Default")
      (node (ref "U14") (pin "H3") (pinfunction "DQ4_H3") (pintype "passive"))
    )
    (net (code "28") (name "/DDR3_DQ5") (class "Default")
      (node (ref "U14") (pin "H8") (pinfunction "DQ5_H8") (pintype "passive"))
    )
    (net (code "29") (name "/DDR3_DQ6") (class "Default")
      (node (ref "U14") (pin "G2") (pinfunction "DQ6_G2") (pintype "passive"))
    )
    (net (code "30") (name "/DDR3_DQ7") (class "Default")
      (node (ref "U14") (pin "H7") (pinfunction "DQ7_H7") (pintype "passive"))
    )
    (net (code "31") (name "/DDR3_DQ8") (class "Default")
      (node (ref "U14") (pin "D7") (pinfunction "DQ8_D7") (pintype "passive"))
    )
    (net (code "32") (name "/DDR3_DQ9") (class "Default")
      (node (ref "U14") (pin "C3") (pinfunction "DQ9_C3") (pintype "passive"))
    )
    (net (code "33") (name "/DDR3_DQ10") (class "Default")
      (node (ref "U14") (pin "C8") (pinfunction "DQ10_C8") (pintype "passive"))
    )
    (net (code "34") (name "/DDR3_DQ11") (class "Default")
      (node (ref "U14") (pin "C2") (pinfunction "DQ11_C2") (pintype "passive"))
    )
    (net (code "35") (name "/DDR3_DQ12") (class "Default")
      (node (ref "U14") (pin "A7") (pinfunction "DQ12_A7") (pintype "passive"))
    )
    (net (code "36") (name "/DDR3_DQ13") (class "Default")
      (node (ref "U14") (pin "A2") (pinfunction "DQ13_A2") (pintype "passive"))
    )
    (net (code "37") (name "/DDR3_DQ14") (class "Default")
      (node (ref "U14") (pin "B8") (pinfunction "DQ14_B8") (pintype "passive"))
    )
    (net (code "38") (name "/DDR3_DQ15") (class "Default")
      (node (ref "U14") (pin "A3") (pinfunction "DQ15_A3") (pintype "passive"))
    )
    (net (code "39") (name "/DDR3_LDM") (class "Default")
      (node (ref "U14") (pin "E7") (pinfunction "LDM_E7") (pintype "input"))
    )
    (net (code "40") (name "/DDR3_LDQS_N") (class "Default")
      (node (ref "U14") (pin "G3") (pinfunction "LDQS_G3") (pintype "passive"))
    )
    (net (code "41") (name "/DDR3_LDQS_P") (class "Default")
      (node (ref "U14") (pin "F3") (pinfunction "LDQS_F3") (pintype "passive"))
    )
    (net (code "42") (name "/DDR3_ODT") (class "Default")
      (node (ref "R48") (pin "1") (pinfunction "1_1") (pintype "passive"))
      (node (ref "U14") (pin "K1") (pinfunction "ODT_K1") (pintype "passive"))
    )
    (net (code "43") (name "/DDR3_RAS") (class "Default")
      (node (ref "R54") (pin "1") (pinfunction "1_1") (pintype "passive"))
      (node (ref "U14") (pin "J3") (pinfunction "RAS_J3") (pintype "passive"))
    )
    (net (code "44") (name "/DDR3_RESET") (class "Default")
      (node (ref "U14") (pin "T2") (pinfunction "RESET_T2") (pintype "passive"))
    )
    (net (code "45") (name "/DDR3_UDM") (class "Default")
      (node (ref "U14") (pin "D3") (pinfunction "UDM_D3") (pintype "input"))
    )
    (net (code "46") (name "/DDR3_UDQS_N") (class "Default")
      (node (ref "U14") (pin "B7") (pinfunction "UDQS_B7") (pintype "passive"))
    )
    (net (code "47") (name "/DDR3_UDQS_P") (class "Default")
      (node (ref "U14") (pin "C7") (pinfunction "UDQS_C7") (pintype "passive"))
    )
    (net (code "48") (name "/DDR3_WE") (class "Default")
      (node (ref "R56") (pin "1") (pinfunction "1_1") (pintype "passive"))
      (node (ref "U14") (pin "L3") (pinfunction "WE_L3") (pintype "passive"))
    )
    (net (code "49") (name "1V5D") (class "Default")
      (node (ref "C162") (pin "2") (pinfunction "2_2") (pintype "passive"))
      (node (ref "C163") (pin "2") (pinfunction "2_2") (pintype "passive"))
      (node (ref "C164") (pin "2") (pinfunction "2_2") (pintype "passive"))
      (node (ref "C165") (pin "2") (pinfunction "2_2") (pintype "passive"))
      (node (ref "C166") (pin "2") (pinfunction "2_2") (pintype "passive"))
      (node (ref "C167") (pin "2") (pinfunction "2_2") (pintype "passive"))
      (node (ref "C168") (pin "2") (pinfunction "2_2") (pintype "passive"))
      (node (ref "C169") (pin "2") (pinfunction "2_2") (pintype "passive"))
      (node (ref "R58") (pin "2") (pinfunction "2_2") (pintype "passive"))
      (node (ref "U14") (pin "A1") (pinfunction "VDDQ_A1") (pintype "power_in"))
      (node (ref "U14") (pin "A8") (pinfunction "VDDQ_A8") (pintype "power_in"))
      (node (ref "U14") (pin "B2") (pinfunction "VDD_B2") (pintype "power_in"))
      (node (ref "U14") (pin "C1") (pinfunction "VDDQ_C1") (pintype "power_in"))
      (node (ref "U14") (pin "C9") (pinfunction "VDDQ_C9") (pintype "power_in"))
      (node (ref "U14") (pin "D2") (pinfunction "VDDQ_D2") (pintype "power_in"))
      (node (ref "U14") (pin "D9") (pinfunction "VDD_D9") (pintype "power_in"))
      (node (ref "U14") (pin "E9") (pinfunction "VDDQ_E9") (pintype "power_in"))
      (node (ref "U14") (pin "F1") (pinfunction "VDDQ_F1") (pintype "power_in"))
      (node (ref "U14") (pin "G7") (pinfunction "VDD_G7") (pintype "power_in"))
      (node (ref "U14") (pin "H2") (pinfunction "VDDQ_H2") (pintype "power_in"))
      (node (ref "U14") (pin "H9") (pinfunction "VDDQ_H9") (pintype "power_in"))
      (node (ref "U14") (pin "K2") (pinfunction "VDD_K2") (pintype "power_in"))
      (node (ref "U14") (pin "K8") (pinfunction "VDD_K8") (pintype "power_in"))
      (node (ref "U14") (pin "N1") (pinfunction "VDD_N1") (pintype "power_in"))
      (node (ref "U14") (pin "N9") (pinfunction "VDD_N9") (pintype "power_in"))
      (node (ref "U14") (pin "R1") (pinfunction "VDD_R1") (pintype "power_in"))
      (node (ref "U14") (pin "R9") (pinfunction "VDD_R9") (pintype "power_in"))
      (node (ref "U15") (pin "2") (pinfunction "VLDOIN_2") (pintype "passive"))
    )
    (net (code "50") (name "3V3DDR") (class "Default")
      (node (ref "C159") (pin "2") (pinfunction "2_2") (pintype "passive"))
      (node (ref "R57") (pin "2") (pinfunction "2_2") (pintype "passive"))
      (node (ref "U15") (pin "10") (pinfunction "VIN_10") (pintype "passive"))
      (node (ref "U15") (pin "7") (pinfunction "EN_7") (pintype "passive"))
    )
    (net (code "51") (name "DDR3_VTT") (class "Default")
      (node (ref "C124") (pin "2") (pinfunction "2_2") (pintype "passive"))
      (node (ref "C125") (pin "2") (pinfunction "2_2") (pintype "passive"))
      (node (ref "C126") (pin "2") (pinfunction "2_2") (pintype "passive"))
      (node (ref "C129") (pin "2") (pinfunction "2_2") (pintype "passive"))
      (node (ref "C130") (pin "2") (pinfunction "2_2") (pintype "passive"))
      (node (ref "C131") (pin "2") (pinfunction "2_2") (pintype "passive"))
      (node (ref "C132") (pin "2") (pinfunction "2_2") (pintype "passive"))
      (node (ref "C133") (pin "2") (pinfunction "2_2") (pintype "passive"))
      (node (ref "C134") (pin "2") (pinfunction "2_2") (pintype "passive"))
      (node (ref "C135") (pin "2") (pinfunction "2_2") (pintype "passive"))
      (node (ref "C136") (pin "2") (pinfunction "2_2") (pintype "passive"))
      (node (ref "C137") (pin "2") (pinfunction "2_2") (pintype "passive"))
      (node (ref "C138") (pin "2") (pinfunction "2_2") (pintype "passive"))
      (node (ref "C139") (pin "2") (pinfunction "2_2") (pintype "passive"))
      (node (ref "C140") (pin "2") (pinfunction "2_2") (pintype "passive"))
      (node (ref "C141") (pin "2") (pinfunction "2_2") (pintype "passive"))
      (node (ref "C142") (pin "2") (pinfunction "2_2") (pintype "passive"))
      (node (ref "C143") (pin "2") (pinfunction "2_2") (pintype "passive"))
      (node (ref "C144") (pin "2") (pinfunction "2_2") (pintype "passive"))
      (node (ref "C145") (pin "2") (pinfunction "2_2") (pintype "passive"))
      (node (ref "C146") (pin "2") (pinfunction "2_2") (pintype "passive"))
      (node (ref "C147") (pin "2") (pinfunction "2_2") (pintype "passive"))
      (node (ref "C148") (pin "2") (pinfunction "2_2") (pintype "passive"))
      (node (ref "C149") (pin "2") (pinfunction "2_2") (pintype "passive"))
      (node (ref "C150") (pin "2") (pinfunction "2_2") (pintype "passive"))
      (node (ref "C151") (pin "2") (pinfunction "2_2") (pintype "passive"))
      (node (ref "C152") (pin "2") (pinfunction "2_2") (pintype "passive"))
      (node (ref "C153") (pin "2") (pinfunction "2_2") (pintype "passive"))
      (node (ref "C154") (pin "2") (pinfunction "2_2") (pintype "passive"))
      (node (ref "C155") (pin "2") (pinfunction "2_2") (pintype "passive"))
      (node (ref "C156") (pin "2") (pinfunction "2_2") (pintype "passive"))
      (node (ref "C157") (pin "2") (pinfunction "2_2") (pintype "passive"))
      (node (ref "C158") (pin "2") (pinfunction "2_2") (pintype "passive"))
      (node (ref "R34") (pin "2") (pinfunction "2_2") (pintype "passive"))
      (node (ref "R35") (pin "2") (pinfunction "2_2") (pintype "passive"))
      (node (ref "R36") (pin "2") (pinfunction "2_2") (pintype "passive"))
      (node (ref "R37") (pin "2") (pinfunction "2_2") (pintype "passive"))
      (node (ref "R38") (pin "2") (pinfunction "2_2") (pintype "passive"))
      (node (ref "R39") (pin "2") (pinfunction "2_2") (pintype "passive"))
      (node (ref "R40") (pin "2") (pinfunction "2_2") (pintype "passive"))
      (node (ref "R41") (pin "2") (pinfunction "2_2") (pintype "passive"))
      (node (ref "R42") (pin "2") (pinfunction "2_2") (pintype "passive"))
      (node (ref "R43") (pin "2") (pinfunction "2_2") (pintype "passive"))
      (node (ref "R44") (pin "2") (pinfunction "2_2") (pintype "passive"))
      (node (ref "R45") (pin "2") (pinfunction "2_2") (pintype "passive"))
      (node (ref "R46") (pin "2") (pinfunction "2_2") (pintype "passive"))
      (node (ref "R47") (pin "2") (pinfunction "2_2") (pintype "passive"))
      (node (ref "R48") (pin "2") (pinfunction "2_2") (pintype "passive"))
      (node (ref "R49") (pin "2") (pinfunction "2_2") (pintype "passive"))
      (node (ref "R50") (pin "2") (pinfunction "2_2") (pintype "passive"))
      (node (ref "R51") (pin "2") (pinfunction "2_2") (pintype "passive"))
      (node (ref "R52") (pin "2") (pinfunction "2_2") (pintype "passive"))
      (node (ref "R53") (pin "2") (pinfunction "2_2") (pintype "passive"))
      (node (ref "R54") (pin "2") (pinfunction "2_2") (pintype "passive"))
      (node (ref "R55") (pin "2") (pinfunction "2_2") (pintype "passive"))
      (node (ref "R56") (pin "2") (pinfunction "2_2") (pintype "passive"))
      (node (ref "U15") (pin "3") (pinfunction "VO_3") (pintype "passive"))
      (node (ref "U15") (pin "5") (pinfunction "VOSNS_5") (pintype "passive"))
    )
    (net (code "52") (name "DDR_VREF") (class "Default")
      (node (ref "C128") (pin "2") (pinfunction "2_2") (pintype "passive"))
      (node (ref "C160") (pin "2") (pinfunction "2_2") (pintype "passive"))
      (node (ref "C161") (pin "2") (pinfunction "2_2") (pintype "passive"))
      (node (ref "U14") (pin "H1") (pinfunction "VREFDQ_H1") (pintype "passive"))
      (node (ref "U14") (pin "M8") (pinfunction "VREFCA_M8") (pintype "passive"))
      (node (ref "U15") (pin "6") (pinfunction "REFOUT_6") (pintype "passive"))
    )
    (net (code "53") (name "GND") (class "Default")
      (node (ref "C124") (pin "1") (pinfunction "1_1") (pintype "passive"))
      (node (ref "C125") (pin "1") (pinfunction "1_1") (pintype "passive"))
      (node (ref "C126") (pin "1") (pinfunction "1_1") (pintype "passive"))
      (node (ref "C127") (pin "1") (pinfunction "1_1") (pintype "passive"))
      (node (ref "C128") (pin "1") (pinfunction "1_1") (pintype "passive"))
      (node (ref "C129") (pin "1") (pinfunction "1_1") (pintype "passive"))
      (node (ref "C130") (pin "1") (pinfunction "1_1") (pintype "passive"))
      (node (ref "C131") (pin "1") (pinfunction "1_1") (pintype "passive"))
      (node (ref "C132") (pin "1") (pinfunction "1_1") (pintype "passive"))
      (node (ref "C133") (pin "1") (pinfunction "1_1") (pintype "passive"))
      (node (ref "C134") (pin "1") (pinfunction "1_1") (pintype "passive"))
      (node (ref "C135") (pin "1") (pinfunction "1_1") (pintype "passive"))
      (node (ref "C136") (pin "1") (pinfunction "1_1") (pintype "passive"))
      (node (ref "C137") (pin "1") (pinfunction "1_1") (pintype "passive"))
      (node (ref "C138") (pin "1") (pinfunction "1_1") (pintype "passive"))
      (node (ref "C139") (pin "1") (pinfunction "1_1") (pintype "passive"))
      (node (ref "C140") (pin "1") (pinfunction "1_1") (pintype "passive"))
      (node (ref "C141") (pin "1") (pinfunction "1_1") (pintype "passive"))
      (node (ref "C142") (pin "1") (pinfunction "1_1") (pintype "passive"))
      (node (ref "C143") (pin "1") (pinfunction "1_1") (pintype "passive"))
      (node (ref "C144") (pin "1") (pinfunction "1_1") (pintype "passive"))
      (node (ref "C145") (pin "1") (pinfunction "1_1") (pintype "passive"))
      (node (ref "C146") (pin "1") (pinfunction "1_1") (pintype "passive"))
      (node (ref "C147") (pin "1") (pinfunction "1_1") (pintype "passive"))
      (node (ref "C148") (pin "1") (pinfunction "1_1") (pintype "passive"))
      (node (ref "C149") (pin "1") (pinfunction "1_1") (pintype "passive"))
      (node (ref "C150") (pin "1") (pinfunction "1_1") (pintype "passive"))
      (node (ref "C151") (pin "1") (pinfunction "1_1") (pintype "passive"))
      (node (ref "C152") (pin "1") (pinfunction "1_1") (pintype "passive"))
      (node (ref "C153") (pin "1") (pinfunction "1_1") (pintype "passive"))
      (node (ref "C154") (pin "1") (pinfunction "1_1") (pintype "passive"))
      (node (ref "C155") (pin "1") (pinfunction "1_1") (pintype "passive"))
      (node (ref "C156") (pin "1") (pinfunction "1_1") (pintype "passive"))
      (node (ref "C157") (pin "1") (pinfunction "1_1") (pintype "passive"))
      (node (ref "C158") (pin "1") (pinfunction "1_1") (pintype "passive"))
      (node (ref "C159") (pin "1") (pinfunction "1_1") (pintype "passive"))
      (node (ref "C160") (pin "1") (pinfunction "1_1") (pintype "passive"))
      (node (ref "C161") (pin "1") (pinfunction "1_1") (pintype "passive"))
      (node (ref "C162") (pin "1") (pinfunction "1_1") (pintype "passive"))
      (node (ref "C163") (pin "1") (pinfunction "1_1") (pintype "passive"))
      (node (ref "C164") (pin "1") (pinfunction "1_1") (pintype "passive"))
      (node (ref "C165") (pin "1") (pinfunction "1_1") (pintype "passive"))
      (node (ref "C166") (pin "1") (pinfunction "1_1") (pintype "passive"))
      (node (ref "C167") (pin "1") (pinfunction "1_1") (pintype "passive"))
      (node (ref "C168") (pin "1") (pinfunction "1_1") (pintype "passive"))
      (node (ref "C169") (pin "1") (pinfunction "1_1") (pintype "passive"))
      (node (ref "R59") (pin "1") (pinfunction "1_1") (pintype "passive"))
      (node (ref "R60") (pin "1") (pinfunction "1_1") (pintype "passive"))
      (node (ref "U14") (pin "A9") (pinfunction "VSS_A9") (pintype "passive"))
      (node (ref "U14") (pin "B1") (pinfunction "VSSQ_B1") (pintype "passive"))
      (node (ref "U14") (pin "B3") (pinfunction "VSS_B3") (pintype "passive"))
      (node (ref "U14") (pin "B9") (pinfunction "VSSQ_B9") (pintype "passive"))
      (node (ref "U14") (pin "D1") (pinfunction "VSSQ_D1") (pintype "passive"))
      (node (ref "U14") (pin "D8") (pinfunction "VSSQ_D8") (pintype "passive"))
      (node (ref "U14") (pin "E1") (pinfunction "VSS_E1") (pintype "passive"))
      (node (ref "U14") (pin "E2") (pinfunction "VSSQ_E2") (pintype "passive"))
      (node (ref "U14") (pin "E8") (pinfunction "VSSQ_E8") (pintype "passive"))
      (node (ref "U14") (pin "F9") (pinfunction "VSSQ_F9") (pintype "passive"))
      (node (ref "U14") (pin "G1") (pinfunction "VSSQ_G1") (pintype "passive"))
      (node (ref "U14") (pin "G8") (pinfunction "VSS_G8") (pintype "passive"))
      (node (ref "U14") (pin "G9") (pinfunction "VSSQ_G9") (pintype "passive"))
      (node (ref "U14") (pin "J2") (pinfunction "VSS_J2") (pintype "passive"))
      (node (ref "U14") (pin "J8") (pinfunction "VSS_J8") (pintype "passive"))
      (node (ref "U14") (pin "M1") (pinfunction "VSS_M1") (pintype "passive"))
      (node (ref "U14") (pin "M9") (pinfunction "VSS_M9") (pintype "passive"))
      (node (ref "U14") (pin "P1") (pinfunction "VSS_P1") (pintype "passive"))
      (node (ref "U14") (pin "P9") (pinfunction "VSS_P9") (pintype "passive"))
      (node (ref "U14") (pin "T1") (pinfunction "VSS_T1") (pintype "passive"))
      (node (ref "U14") (pin "T9") (pinfunction "VSS_T9") (pintype "passive"))
      (node (ref "U15") (pin "11") (pinfunction "EP_11") (pintype "passive"))
      (node (ref "U15") (pin "4") (pinfunction "PGND_4") (pintype "passive"))
      (node (ref "U15") (pin "8") (pinfunction "GND_8") (pintype "passive"))
    )
    (net (code "54") (name "Net-(U14-ZQ)") (class "Default")
      (node (ref "R60") (pin "2") (pinfunction "2_2") (pintype "passive"))
      (node (ref "U14") (pin "L8") (pinfunction "ZQ_L8") (pintype "passive"))
    )
    (net (code "55") (name "Net-(U15-PGOOD)") (class "Default")
      (node (ref "R57") (pin "1") (pinfunction "1_1") (pintype "passive"))
      (node (ref "U15") (pin "9") (pinfunction "PGOOD_9") (pintype "passive"))
    )
    (net (code "56") (name "Net-(U15-REFIN)") (class "Default")
      (node (ref "C127") (pin "2") (pinfunction "2_2") (pintype "passive"))
      (node (ref "R58") (pin "1") (pinfunction "1_1") (pintype "passive"))
      (node (ref "R59") (pin "2") (pinfunction "2_2") (pintype "passive"))
      (node (ref "U15") (pin "1") (pinfunction "REFIN_1") (pintype "passive"))
    )
    (net (code "57") (name "unconnected-(U14-NC-PadJ1)") (class "Default")
      (node (ref "U14") (pin "J1") (pinfunction "NC_J1") (pintype "passive+no_connect"))
    )
    (net (code "58") (name "unconnected-(U14-NC-PadJ9)") (class "Default")
      (node (ref "U14") (pin "J9") (pinfunction "NC_J9") (pintype "passive+no_connect"))
    )
    (net (code "59") (name "unconnected-(U14-NC-PadL1)") (class "Default")
      (node (ref "U14") (pin "L1") (pinfunction "NC_L1") (pintype "passive+no_connect"))
    )
    (net (code "60") (name "unconnected-(U14-NC-PadL9)") (class "Default")
      (node (ref "U14") (pin "L9") (pinfunction "NC_L9") (pintype "passive+no_connect"))
    )
    (net (code "61") (name "unconnected-(U14-NC-PadM7)") (class "Default")
      (node (ref "U14") (pin "M7") (pinfunction "NC_M7") (pintype "passive+no_connect"))
    )
    (net (code "62") (name "unconnected-(U14-NC-PadT7)") (class "Default")
      (node (ref "U14") (pin "T7") (pinfunction "NC_T7") (pintype "passive+no_connect"))
    )
  )
)
